# Arduino_Robotics_Camp_Tank.net
KiCad netlist of a schematic drawn in EAGLE
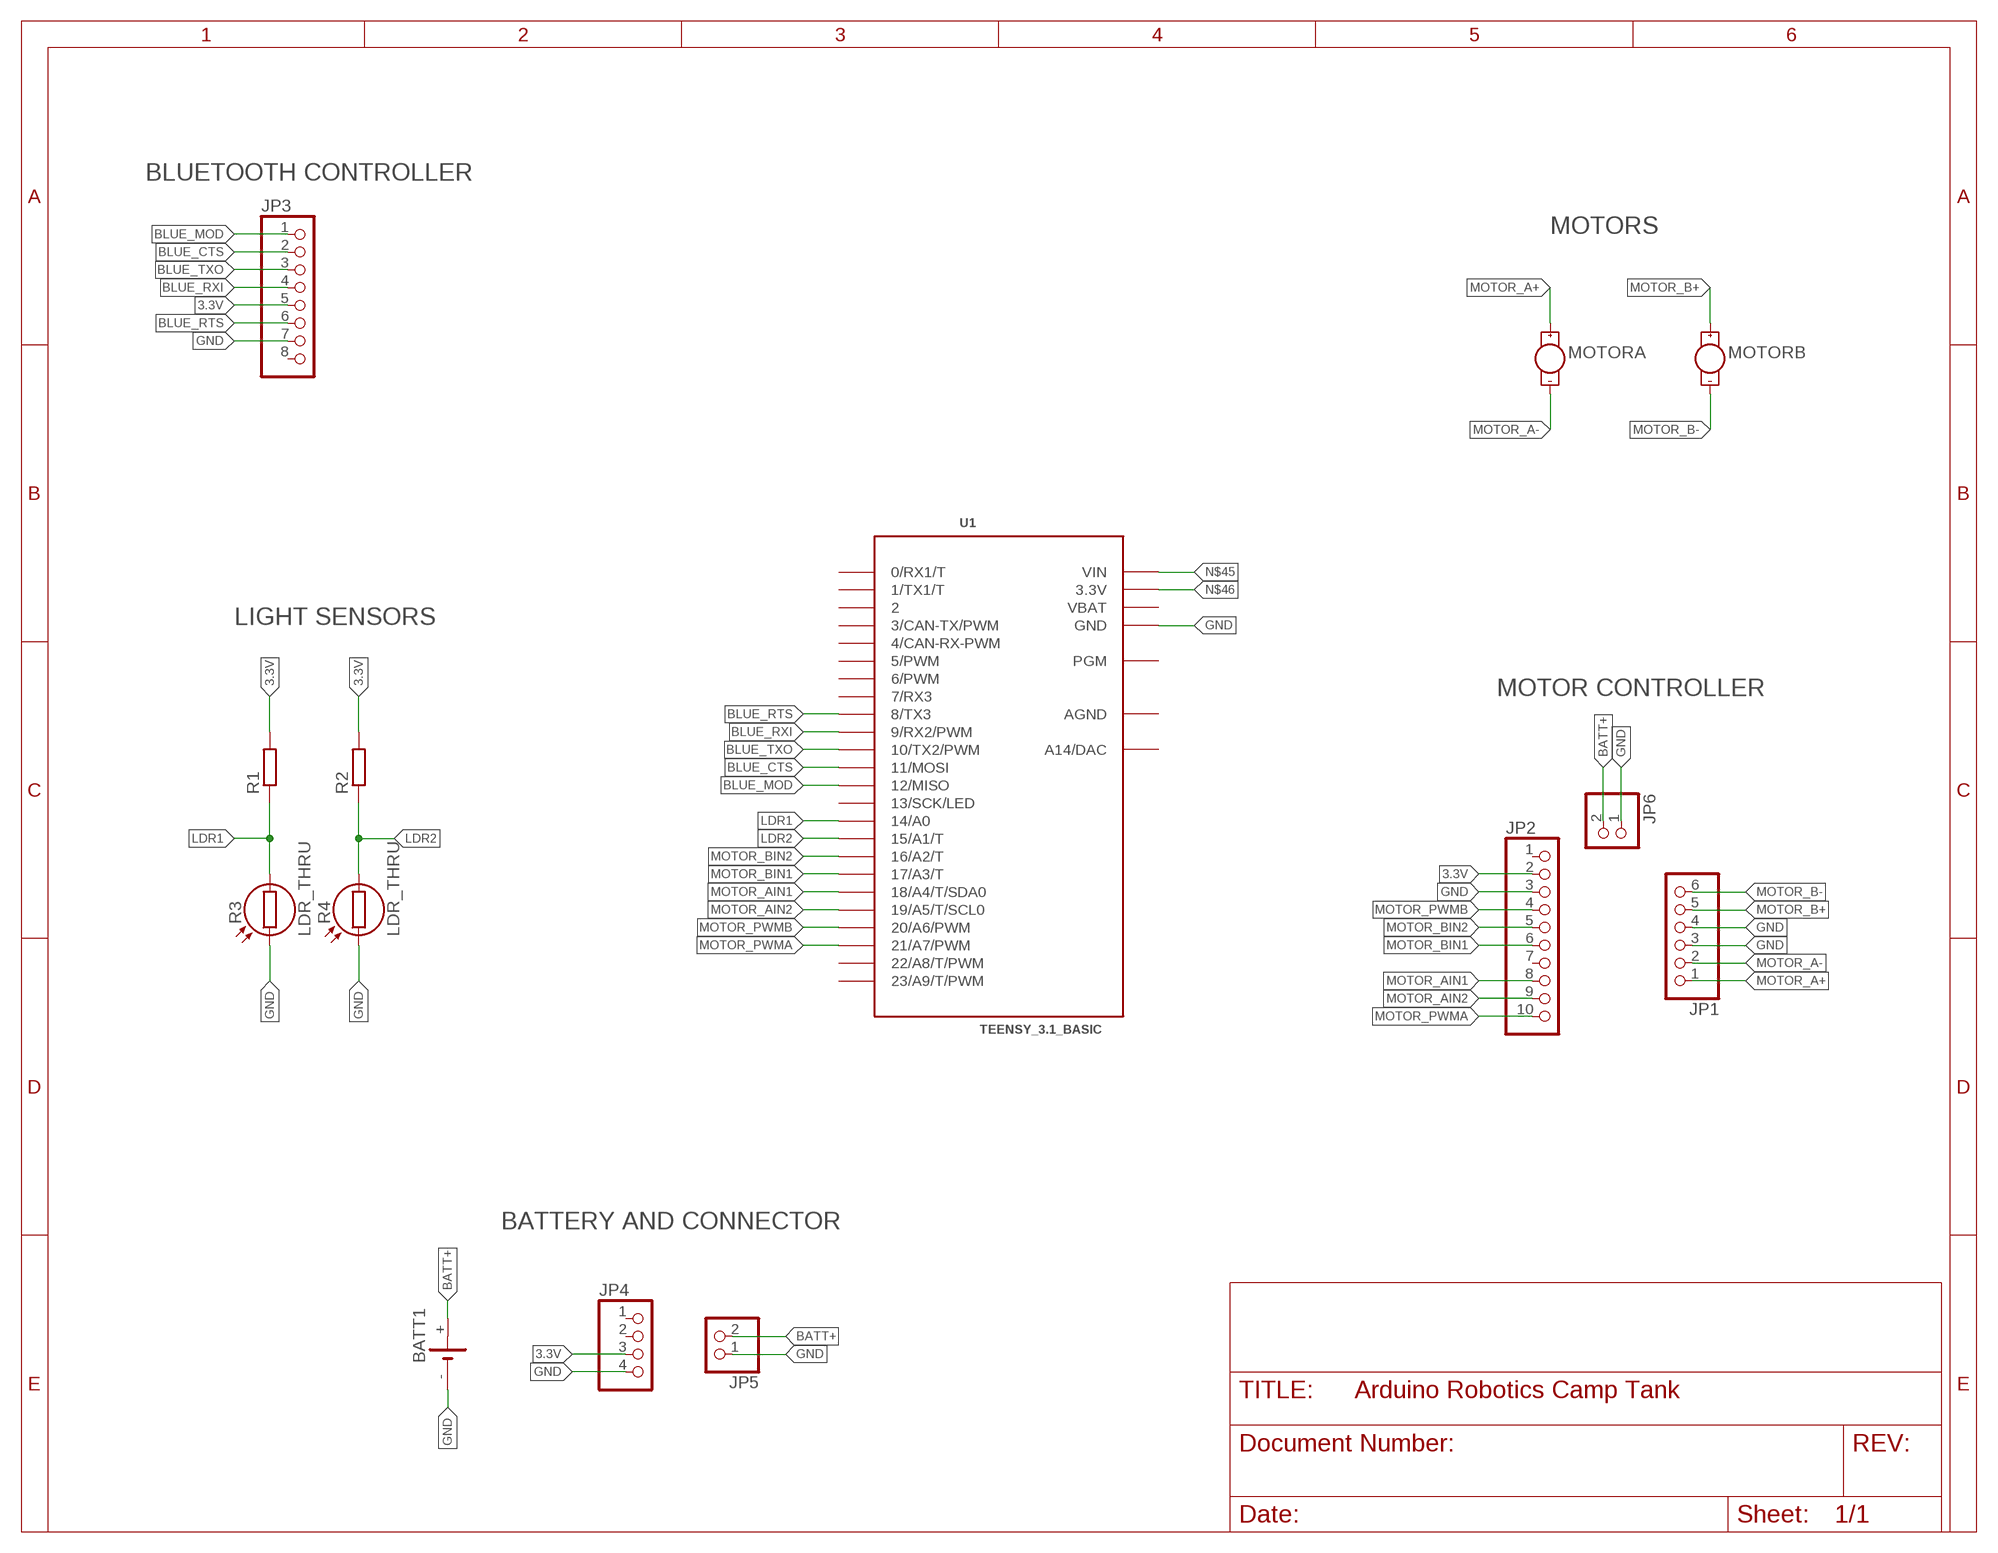
[diagram p0: schematic, sheet 1]

(export (version "E")
  (design (tool "Eeschema 10.0.6"))
  (components
    (comp (ref "BATT1")
      (value "BATT_9V")
      (footprint "eagle-import:9V_CONNECTOR")
      (libsource (lib "eagle-import") (part "BATT_9V"))
    )
    (comp (ref "JP1")
      (value "PINHD-1X6")
      (footprint "eagle-import:1X06")
      (libsource (lib "eagle-import") (part "PINHD-1X6"))
    )
    (comp (ref "JP2")
      (value "PINHD-1X10")
      (footprint "eagle-import:1X10")
      (libsource (lib "eagle-import") (part "PINHD-1X10"))
    )
    (comp (ref "JP3")
      (value "PINHD-1X8")
      (footprint "eagle-import:1X08")
      (libsource (lib "eagle-import") (part "PINHD-1X8"))
    )
    (comp (ref "JP4")
      (value "PINHD-1X4")
      (footprint "eagle-import:1X04")
      (libsource (lib "eagle-import") (part "PINHD-1X4"))
    )
    (comp (ref "JP5")
      (value "PINHD-1X2")
      (footprint "eagle-import:1X02")
      (libsource (lib "eagle-import") (part "PINHD-1X2"))
    )
    (comp (ref "JP6")
      (value "PINHD-1X2")
      (footprint "eagle-import:1X02")
      (libsource (lib "eagle-import") (part "PINHD-1X2"))
    )
    (comp (ref "MOTORA")
      (value "MOTOR10MM")
      (footprint "eagle-import:VIBE-MOTOR-10MM")
      (libsource (lib "eagle-import") (part "MOTOR10MM"))
    )
    (comp (ref "MOTORB")
      (value "MOTOR10MM")
      (footprint "eagle-import:VIBE-MOTOR-10MM")
      (libsource (lib "eagle-import") (part "MOTOR10MM"))
    )
    (comp (ref "R1")
      (value "R-EU_0204/7")
      (footprint "eagle-import:0204_7")
      (libsource (lib "eagle-import") (part "R-EU_0204/7"))
    )
    (comp (ref "R2")
      (value "R-EU_0204/7")
      (footprint "eagle-import:0204_7")
      (libsource (lib "eagle-import") (part "R-EU_0204/7"))
    )
    (comp (ref "R3")
      (value "LDR_THRU")
      (footprint "eagle-import:LDR")
      (libsource (lib "eagle-import") (part "LDR_THRU"))
    )
    (comp (ref "R4")
      (value "LDR_THRU")
      (footprint "eagle-import:LDR")
      (libsource (lib "eagle-import") (part "LDR_THRU"))
    )
    (comp (ref "U1")
      (value "TEENSY_3.1_BASIC")
      (footprint "eagle-import:TEENSY_3.1_BASIC")
      (libsource (lib "eagle-import") (part "TEENSY_3.1_BASIC"))
    )
  )
  (nets
    (net (code "1") (name "/AGND") (class "Default")
      (node (ref "U1") (pin "AGND") (pinfunction "AGND_AGND") (pintype "power_in"))
    )
    (net (code "2") (name "/VBAT") (class "Default")
      (node (ref "U1") (pin "VBAT") (pinfunction "VBAT_VBAT") (pintype "power_in"))
    )
    (net (code "3") (name "3.3V") (class "Default")
      (node (ref "JP2") (pin "2") (pinfunction "2_2") (pintype "passive"))
      (node (ref "JP3") (pin "5") (pinfunction "5_5") (pintype "passive"))
      (node (ref "JP4") (pin "3") (pinfunction "3_3") (pintype "passive"))
      (node (ref "R1") (pin "2") (pinfunction "2_2") (pintype "passive"))
      (node (ref "R2") (pin "2") (pinfunction "2_2") (pintype "passive"))
    )
    (net (code "4") (name "BATT+") (class "Default")
      (node (ref "BATT1") (pin "+") (pinfunction "+_+") (pintype "passive"))
      (node (ref "JP5") (pin "2") (pinfunction "2_2") (pintype "passive"))
      (node (ref "JP6") (pin "2") (pinfunction "2_2") (pintype "passive"))
    )
    (net (code "5") (name "BLUE_CTS") (class "Default")
      (node (ref "JP3") (pin "2") (pinfunction "2_2") (pintype "passive"))
      (node (ref "U1") (pin "11") (pinfunction "11/MOSI_11") (pintype "bidirectional"))
    )
    (net (code "6") (name "BLUE_MOD") (class "Default")
      (node (ref "JP3") (pin "1") (pinfunction "1_1") (pintype "passive"))
      (node (ref "U1") (pin "12") (pinfunction "12/MISO_12") (pintype "bidirectional"))
    )
    (net (code "7") (name "BLUE_RTS") (class "Default")
      (node (ref "JP3") (pin "6") (pinfunction "6_6") (pintype "passive"))
      (node (ref "U1") (pin "8") (pinfunction "8/TX3_8") (pintype "bidirectional"))
    )
    (net (code "8") (name "BLUE_RXI") (class "Default")
      (node (ref "JP3") (pin "4") (pinfunction "4_4") (pintype "passive"))
      (node (ref "U1") (pin "9") (pinfunction "9/RX2/PWM_9") (pintype "bidirectional"))
    )
    (net (code "9") (name "BLUE_TXO") (class "Default")
      (node (ref "JP3") (pin "3") (pinfunction "3_3") (pintype "passive"))
      (node (ref "U1") (pin "10") (pinfunction "10/TX2/PWM_10") (pintype "bidirectional"))
    )
    (net (code "10") (name "GND") (class "Default")
      (node (ref "BATT1") (pin "-") (pinfunction "-_-") (pintype "passive"))
      (node (ref "JP1") (pin "3") (pinfunction "3_3") (pintype "passive"))
      (node (ref "JP1") (pin "4") (pinfunction "4_4") (pintype "passive"))
      (node (ref "JP2") (pin "3") (pinfunction "3_3") (pintype "passive"))
      (node (ref "JP3") (pin "7") (pinfunction "7_7") (pintype "passive"))
      (node (ref "JP4") (pin "4") (pinfunction "4_4") (pintype "passive"))
      (node (ref "JP5") (pin "1") (pinfunction "1_1") (pintype "passive"))
      (node (ref "JP6") (pin "1") (pinfunction "1_1") (pintype "passive"))
      (node (ref "R3") (pin "1") (pinfunction "1_1") (pintype "passive"))
      (node (ref "R4") (pin "1") (pinfunction "1_1") (pintype "passive"))
      (node (ref "U1") (pin "GND") (pinfunction "GND_GND") (pintype "power_in"))
      (node (ref "U1") (pin "GND1") (pinfunction "GND_GND1") (pintype "power_in"))
    )
    (net (code "11") (name "LDR1") (class "Default")
      (node (ref "R1") (pin "1") (pinfunction "1_1") (pintype "passive"))
      (node (ref "R3") (pin "2") (pinfunction "2_2") (pintype "passive"))
      (node (ref "U1") (pin "14/A0") (pinfunction "14/A0_14/A0") (pintype "bidirectional"))
    )
    (net (code "12") (name "LDR2") (class "Default")
      (node (ref "R2") (pin "1") (pinfunction "1_1") (pintype "passive"))
      (node (ref "R4") (pin "2") (pinfunction "2_2") (pintype "passive"))
      (node (ref "U1") (pin "15/A1") (pinfunction "15/A1/T_15/A1") (pintype "bidirectional"))
    )
    (net (code "13") (name "MOTOR_A+") (class "Default")
      (node (ref "JP1") (pin "1") (pinfunction "1_1") (pintype "passive"))
      (node (ref "MOTORA") (pin "+") (pinfunction "+_+") (pintype "bidirectional"))
    )
    (net (code "14") (name "MOTOR_A-") (class "Default")
      (node (ref "JP1") (pin "2") (pinfunction "2_2") (pintype "passive"))
      (node (ref "MOTORA") (pin "-") (pinfunction "-_-") (pintype "bidirectional"))
    )
    (net (code "15") (name "MOTOR_AIN1") (class "Default")
      (node (ref "JP2") (pin "8") (pinfunction "8_8") (pintype "passive"))
      (node (ref "U1") (pin "18/A4") (pinfunction "18/A4/T/SDA0_18/A4") (pintype "bidirectional"))
    )
    (net (code "16") (name "MOTOR_AIN2") (class "Default")
      (node (ref "JP2") (pin "9") (pinfunction "9_9") (pintype "passive"))
      (node (ref "U1") (pin "19/A5") (pinfunction "19/A5/T/SCL0_19/A5") (pintype "bidirectional"))
    )
    (net (code "17") (name "MOTOR_B+") (class "Default")
      (node (ref "JP1") (pin "5") (pinfunction "5_5") (pintype "passive"))
      (node (ref "MOTORB") (pin "+") (pinfunction "+_+") (pintype "bidirectional"))
    )
    (net (code "18") (name "MOTOR_B-") (class "Default")
      (node (ref "JP1") (pin "6") (pinfunction "6_6") (pintype "passive"))
      (node (ref "MOTORB") (pin "-") (pinfunction "-_-") (pintype "bidirectional"))
    )
    (net (code "19") (name "MOTOR_BIN1") (class "Default")
      (node (ref "JP2") (pin "6") (pinfunction "6_6") (pintype "passive"))
      (node (ref "U1") (pin "17/A3") (pinfunction "17/A3/T_17/A3") (pintype "bidirectional"))
    )
    (net (code "20") (name "MOTOR_BIN2") (class "Default")
      (node (ref "JP2") (pin "5") (pinfunction "5_5") (pintype "passive"))
      (node (ref "U1") (pin "16/A2") (pinfunction "16/A2/T_16/A2") (pintype "bidirectional"))
    )
    (net (code "21") (name "MOTOR_PWMA") (class "Default")
      (node (ref "JP2") (pin "10") (pinfunction "10_10") (pintype "passive"))
      (node (ref "U1") (pin "21/A7") (pinfunction "21/A7/PWM_21/A7") (pintype "bidirectional"))
    )
    (net (code "22") (name "MOTOR_PWMB") (class "Default")
      (node (ref "JP2") (pin "4") (pinfunction "4_4") (pintype "passive"))
      (node (ref "U1") (pin "20/A6") (pinfunction "20/A6/PWM_20/A6") (pintype "bidirectional"))
    )
    (net (code "23") (name "N$45") (class "Default")
      (node (ref "U1") (pin "VIN") (pinfunction "VIN_VIN") (pintype "power_in"))
    )
    (net (code "24") (name "N$46") (class "Default")
      (node (ref "U1") (pin "3.3V") (pinfunction "3.3V_3.3V") (pintype "power_in"))
      (node (ref "U1") (pin "3.3V1") (pinfunction "3.3V_3.3V1") (pintype "power_in"))
    )
    (net (code "25") (name "unconnected-(JP2-Pad1)") (class "Default")
      (node (ref "JP2") (pin "1") (pinfunction "1_1") (pintype "passive"))
    )
    (net (code "26") (name "unconnected-(JP2-Pad7)") (class "Default")
      (node (ref "JP2") (pin "7") (pinfunction "7_7") (pintype "passive"))
    )
    (net (code "27") (name "unconnected-(JP3-Pad8)") (class "Default")
      (node (ref "JP3") (pin "8") (pinfunction "8_8") (pintype "passive"))
    )
    (net (code "28") (name "unconnected-(JP4-Pad1)") (class "Default")
      (node (ref "JP4") (pin "1") (pinfunction "1_1") (pintype "passive"))
    )
    (net (code "29") (name "unconnected-(JP4-Pad2)") (class "Default")
      (node (ref "JP4") (pin "2") (pinfunction "2_2") (pintype "passive"))
    )
    (net (code "30") (name "unconnected-(U1-0{slash}RX1{slash}T-Pad0)") (class "Default")
      (node (ref "U1") (pin "0") (pinfunction "0/RX1/T_0") (pintype "bidirectional"))
    )
    (net (code "31") (name "unconnected-(U1-1{slash}TX1{slash}T-Pad1)") (class "Default")
      (node (ref "U1") (pin "1") (pinfunction "1/TX1/T_1") (pintype "bidirectional"))
    )
    (net (code "32") (name "unconnected-(U1-3{slash}CAN-TX{slash}PWM-Pad3)") (class "Default")
      (node (ref "U1") (pin "3") (pinfunction "3/CAN-TX/PWM_3") (pintype "bidirectional"))
    )
    (net (code "33") (name "unconnected-(U1-4{slash}CAN-RX-PWM-Pad4)") (class "Default")
      (node (ref "U1") (pin "4") (pinfunction "4/CAN-RX-PWM_4") (pintype "bidirectional"))
    )
    (net (code "34") (name "unconnected-(U1-5{slash}PWM-Pad5)") (class "Default")
      (node (ref "U1") (pin "5") (pinfunction "5/PWM_5") (pintype "bidirectional"))
    )
    (net (code "35") (name "unconnected-(U1-6{slash}PWM-Pad6)") (class "Default")
      (node (ref "U1") (pin "6") (pinfunction "6/PWM_6") (pintype "bidirectional"))
    )
    (net (code "36") (name "unconnected-(U1-7{slash}RX3-Pad7)") (class "Default")
      (node (ref "U1") (pin "7") (pinfunction "7/RX3_7") (pintype "bidirectional"))
    )
    (net (code "37") (name "unconnected-(U1-13{slash}SCK{slash}LED-Pad13)") (class "Default")
      (node (ref "U1") (pin "13") (pinfunction "13/SCK/LED_13") (pintype "bidirectional"))
    )
    (net (code "38") (name "unconnected-(U1-22{slash}A8{slash}T{slash}PWM-Pad22{slash}A8)") (class "Default")
      (node (ref "U1") (pin "22/A8") (pinfunction "22/A8/T/PWM_22/A8") (pintype "bidirectional"))
    )
    (net (code "39") (name "unconnected-(U1-23{slash}A9{slash}T{slash}PWM-Pad23{slash}A9)") (class "Default")
      (node (ref "U1") (pin "23/A9") (pinfunction "23/A9/T/PWM_23/A9") (pintype "bidirectional"))
    )
    (net (code "40") (name "unconnected-(U1-A14{slash}DAC-PadA14)") (class "Default")
      (node (ref "U1") (pin "A14") (pinfunction "A14/DAC_A14") (pintype "bidirectional"))
    )
    (net (code "41") (name "unconnected-(U1-Pad2)") (class "Default")
      (node (ref "U1") (pin "2") (pinfunction "2_2") (pintype "bidirectional"))
    )
    (net (code "42") (name "unconnected-(U1-PadPGM)") (class "Default")
      (node (ref "U1") (pin "PGM") (pinfunction "PGM_PGM") (pintype "bidirectional"))
    )
  )
)
